# SD_card.net
KiCad netlist of a schematic drawn in Altium Designer
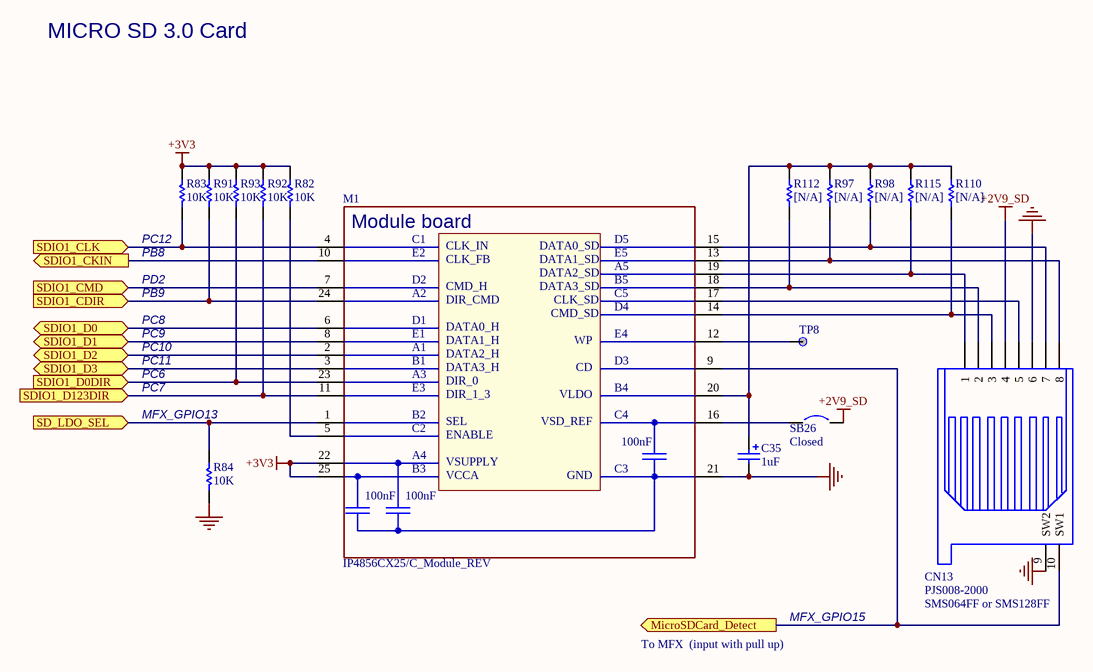
[diagram p0: SD card.SchDoc]

(export (version "E")
  (design (tool "Eeschema 10.0.6"))
  (components
    (comp (ref "C35")
      (value "1uF")
      (footprint "TAN-A")
      (description "Polarized Capacitor (Radial)")
      (fields (field (name "PUBLISHER") "Altium Limited"))
      (libsource (lib "Miscellaneous Devices") (part "Cap Pol1"))
    )
    (comp (ref "CN13")
      (value "PJS008-2000")
      (footprint "MSD_PJS008_")
      (libsource (lib "MB525") (part "SMS016AFA5E"))
    )
    (comp (ref "M1")
      (value "IP4856CX25/C_Module_REV")
      (footprint "WLCSP25_0R4_MOUDLE_REV")
      (description "SDcard3.0 dual voltage level  translator")
      (libsource (lib "MB1246") (part "IP4856CX25/C_Module_REV"))
    )
    (comp (ref "R82")
      (value "10K")
      (footprint "0603R")
      (description "Resistor")
      (fields (field (name "PUBLISHER") "Altium Limited"))
      (libsource (lib "Miscellaneous Devices") (part "Res1"))
    )
    (comp (ref "R83")
      (value "10K")
      (footprint "0603R")
      (description "Resistor")
      (fields (field (name "PUBLISHER") "Altium Limited"))
      (libsource (lib "Miscellaneous Devices") (part "Res1"))
    )
    (comp (ref "R84")
      (value "10K")
      (footprint "0603R")
      (description "Resistor")
      (fields (field (name "PUBLISHER") "Altium Limited"))
      (libsource (lib "Miscellaneous Devices") (part "Res1"))
    )
    (comp (ref "R91")
      (value "10K")
      (footprint "0603R")
      (description "Resistor")
      (fields (field (name "PUBLISHER") "Altium Limited"))
      (libsource (lib "Miscellaneous Devices") (part "Res1"))
    )
    (comp (ref "R92")
      (value "10K")
      (footprint "0603R")
      (description "Resistor")
      (fields (field (name "PUBLISHER") "Altium Limited"))
      (libsource (lib "Miscellaneous Devices") (part "Res1"))
    )
    (comp (ref "R93")
      (value "10K")
      (footprint "0603R")
      (description "Resistor")
      (fields (field (name "PUBLISHER") "Altium Limited"))
      (libsource (lib "Miscellaneous Devices") (part "Res1"))
    )
    (comp (ref "R97")
      (value "[N/A]")
      (footprint "0603R")
      (description "Resistor")
      (fields (field (name "PUBLISHER") "Altium Limited"))
      (libsource (lib "Miscellaneous Devices") (part "res1"))
    )
    (comp (ref "R98")
      (value "[N/A]")
      (footprint "0603R")
      (description "Resistor")
      (fields (field (name "PUBLISHER") "Altium Limited"))
      (libsource (lib "Miscellaneous Devices") (part "res1"))
    )
    (comp (ref "R110")
      (value "[N/A]")
      (footprint "0603R")
      (description "Resistor")
      (fields (field (name "PUBLISHER") "Altium Limited"))
      (libsource (lib "Miscellaneous Devices") (part "res1"))
    )
    (comp (ref "R112")
      (value "[N/A]")
      (footprint "0603R")
      (description "Resistor")
      (fields (field (name "PUBLISHER") "Altium Limited"))
      (libsource (lib "Miscellaneous Devices") (part "res1"))
    )
    (comp (ref "R115")
      (value "[N/A]")
      (footprint "0603R")
      (description "Resistor")
      (fields (field (name "PUBLISHER") "Altium Limited"))
      (libsource (lib "Miscellaneous Devices") (part "res1"))
    )
    (comp (ref "SB26")
      (value "Closed")
      (footprint "SB_0603")
      (description "Circuit Breaker")
      (fields (field (name "PUBLISHER") "Altium Limited"))
      (libsource (lib "MB1165") (part "Circuit Breaker_close"))
    )
    (comp (ref "TP8") (value "~") (footprint "TP") (libsource (lib "*") (part "TP")))
  )
  (nets
    (net (code "1") (name "+2V9_SD") (class "Default")
      (node (ref "CN13") (pin "4") (pinfunction "4_4") (pintype "passive"))
      (node (ref "SB26") (pin "1") (pinfunction "1_1") (pintype "passive"))
    )
    (net (code "2") (name "+3V3") (class "Default")
      (node (ref "M1") (pin "22") (pinfunction "CD_22") (pintype "passive"))
      (node (ref "M1") (pin "25") (pinfunction "GND_25") (pintype "passive"))
      (node (ref "R82") (pin "2") (pinfunction "2_2") (pintype "passive"))
      (node (ref "R83") (pin "2") (pinfunction "2_2") (pintype "passive"))
      (node (ref "R91") (pin "2") (pinfunction "2_2") (pintype "passive"))
      (node (ref "R92") (pin "2") (pinfunction "2_2") (pintype "passive"))
      (node (ref "R93") (pin "2") (pinfunction "2_2") (pintype "passive"))
    )
    (net (code "3") (name "/MicroSDCard_Detect") (class "Default")
      (node (ref "CN13") (pin "10") (pinfunction "SW1_10") (pintype "passive"))
      (node (ref "M1") (pin "9") (pinfunction "DIR_0_9") (pintype "passive"))
    )
    (net (code "4") (name "/SDIO1_CDIR") (class "Default")
      (node (ref "M1") (pin "24") (pinfunction "VSD_REF_24") (pintype "passive"))
      (node (ref "R91") (pin "1") (pinfunction "1_1") (pintype "passive"))
    )
    (net (code "5") (name "/SDIO1_CKIN") (class "Default")
      (node (ref "M1") (pin "10") (pinfunction "DIR_1_3_10") (pintype "passive"))
    )
    (net (code "6") (name "/SDIO1_CLK") (class "Default")
      (node (ref "M1") (pin "4") (pinfunction "DIR_CMD_4") (pintype "passive"))
      (node (ref "R83") (pin "1") (pinfunction "1_1") (pintype "passive"))
    )
    (net (code "7") (name "/SDIO1_CMD") (class "Default")
      (node (ref "M1") (pin "7") (pinfunction "DATA2_H_7") (pintype "passive"))
    )
    (net (code "8") (name "/SDIO1_D0") (class "Default")
      (node (ref "M1") (pin "6") (pinfunction "DATA1_H_6") (pintype "passive"))
    )
    (net (code "9") (name "/SDIO1_D0DIR") (class "Default")
      (node (ref "M1") (pin "23") (pinfunction "VLDO_23") (pintype "passive"))
      (node (ref "R93") (pin "1") (pinfunction "1_1") (pintype "passive"))
    )
    (net (code "10") (name "/SDIO1_D1") (class "Default")
      (node (ref "M1") (pin "8") (pinfunction "DATA3_H_8") (pintype "passive"))
    )
    (net (code "11") (name "/SDIO1_D2") (class "Default")
      (node (ref "M1") (pin "2") (pinfunction "CLK_FB_2") (pintype "passive"))
    )
    (net (code "12") (name "/SDIO1_D3") (class "Default")
      (node (ref "M1") (pin "3") (pinfunction "CMD_H_3") (pintype "passive"))
    )
    (net (code "13") (name "/SDIO1_D123DIR") (class "Default")
      (node (ref "M1") (pin "11") (pinfunction "SEL_11") (pintype "passive"))
      (node (ref "R92") (pin "1") (pinfunction "1_1") (pintype "passive"))
    )
    (net (code "14") (name "/SD_LDO_SEL") (class "Default")
      (node (ref "M1") (pin "1") (pinfunction "CLK_IN_1") (pintype "passive"))
      (node (ref "R84") (pin "2") (pinfunction "2_2") (pintype "passive"))
    )
    (net (code "15") (name "GND") (class "Default")
      (node (ref "C35") (pin "2") (pinfunction "2_2") (pintype "passive"))
      (node (ref "CN13") (pin "6") (pinfunction "6_6") (pintype "passive"))
      (node (ref "CN13") (pin "9") (pinfunction "SW2_9") (pintype "passive"))
      (node (ref "M1") (pin "21") (pinfunction "WP_21") (pintype "passive"))
      (node (ref "R84") (pin "1") (pinfunction "1_1") (pintype "passive"))
    )
    (net (code "16") (name "Net-(M1-CLK_SD)") (class "Default")
      (node (ref "CN13") (pin "1") (pinfunction "1_1") (pintype "passive"))
      (node (ref "M1") (pin "19") (pinfunction "CLK_SD_19") (pintype "passive"))
      (node (ref "R115") (pin "2") (pinfunction "2_2") (pintype "passive"))
    )
    (net (code "17") (name "Net-(M1-CMD_SD)") (class "Default")
      (node (ref "C35") (pin "1") (pinfunction "1_1") (pintype "passive"))
      (node (ref "M1") (pin "20") (pinfunction "CMD_SD_20") (pintype "passive"))
      (node (ref "R110") (pin "1") (pinfunction "1_1") (pintype "passive"))
      (node (ref "R112") (pin "1") (pinfunction "1_1") (pintype "passive"))
      (node (ref "R115") (pin "1") (pinfunction "1_1") (pintype "passive"))
      (node (ref "R97") (pin "1") (pinfunction "1_1") (pintype "passive"))
      (node (ref "R98") (pin "1") (pinfunction "1_1") (pintype "passive"))
    )
    (net (code "18") (name "Net-(M1-DATA0_H)") (class "Default")
      (node (ref "M1") (pin "5") (pinfunction "DATA0_H_5") (pintype "passive"))
      (node (ref "R82") (pin "1") (pinfunction "1_1") (pintype "passive"))
    )
    (net (code "19") (name "Net-(M1-DATA0_SD)") (class "Default")
      (node (ref "CN13") (pin "7") (pinfunction "7_7") (pintype "passive"))
      (node (ref "M1") (pin "15") (pinfunction "DATA0_SD_15") (pintype "passive"))
      (node (ref "R98") (pin "2") (pinfunction "2_2") (pintype "passive"))
    )
    (net (code "20") (name "Net-(M1-DATA1_SD)") (class "Default")
      (node (ref "M1") (pin "16") (pinfunction "DATA1_SD_16") (pintype "passive"))
      (node (ref "SB26") (pin "2") (pinfunction "2_2") (pintype "passive"))
    )
    (net (code "21") (name "Net-(M1-DATA2_SD)") (class "Default")
      (node (ref "CN13") (pin "5") (pinfunction "5_5") (pintype "passive"))
      (node (ref "M1") (pin "17") (pinfunction "DATA2_SD_17") (pintype "passive"))
    )
    (net (code "22") (name "Net-(M1-DATA3_SD)") (class "Default")
      (node (ref "CN13") (pin "2") (pinfunction "2_2") (pintype "passive"))
      (node (ref "M1") (pin "18") (pinfunction "DATA3_SD_18") (pintype "passive"))
      (node (ref "R112") (pin "2") (pinfunction "2_2") (pintype "passive"))
    )
    (net (code "23") (name "Net-(M1-ENABLE)") (class "Default")
      (node (ref "M1") (pin "12") (pinfunction "ENABLE_12") (pintype "passive"))
      (node (ref "TP8") (pin "1") (pinfunction "1_1") (pintype "passive"))
    )
    (net (code "24") (name "Net-(M1-VCCA)") (class "Default")
      (node (ref "CN13") (pin "3") (pinfunction "3_3") (pintype "passive"))
      (node (ref "M1") (pin "14") (pinfunction "VCCA_14") (pintype "passive"))
      (node (ref "R110") (pin "2") (pinfunction "2_2") (pintype "passive"))
    )
    (net (code "25") (name "Net-(M1-VSUPPLY)") (class "Default")
      (node (ref "CN13") (pin "8") (pinfunction "8_8") (pintype "passive"))
      (node (ref "M1") (pin "13") (pinfunction "VSUPPLY_13") (pintype "passive"))
      (node (ref "R97") (pin "2") (pinfunction "2_2") (pintype "passive"))
    )
  )
)
